# CAN_Adaptor.net
KiCad netlist of a schematic drawn in Altium Designer
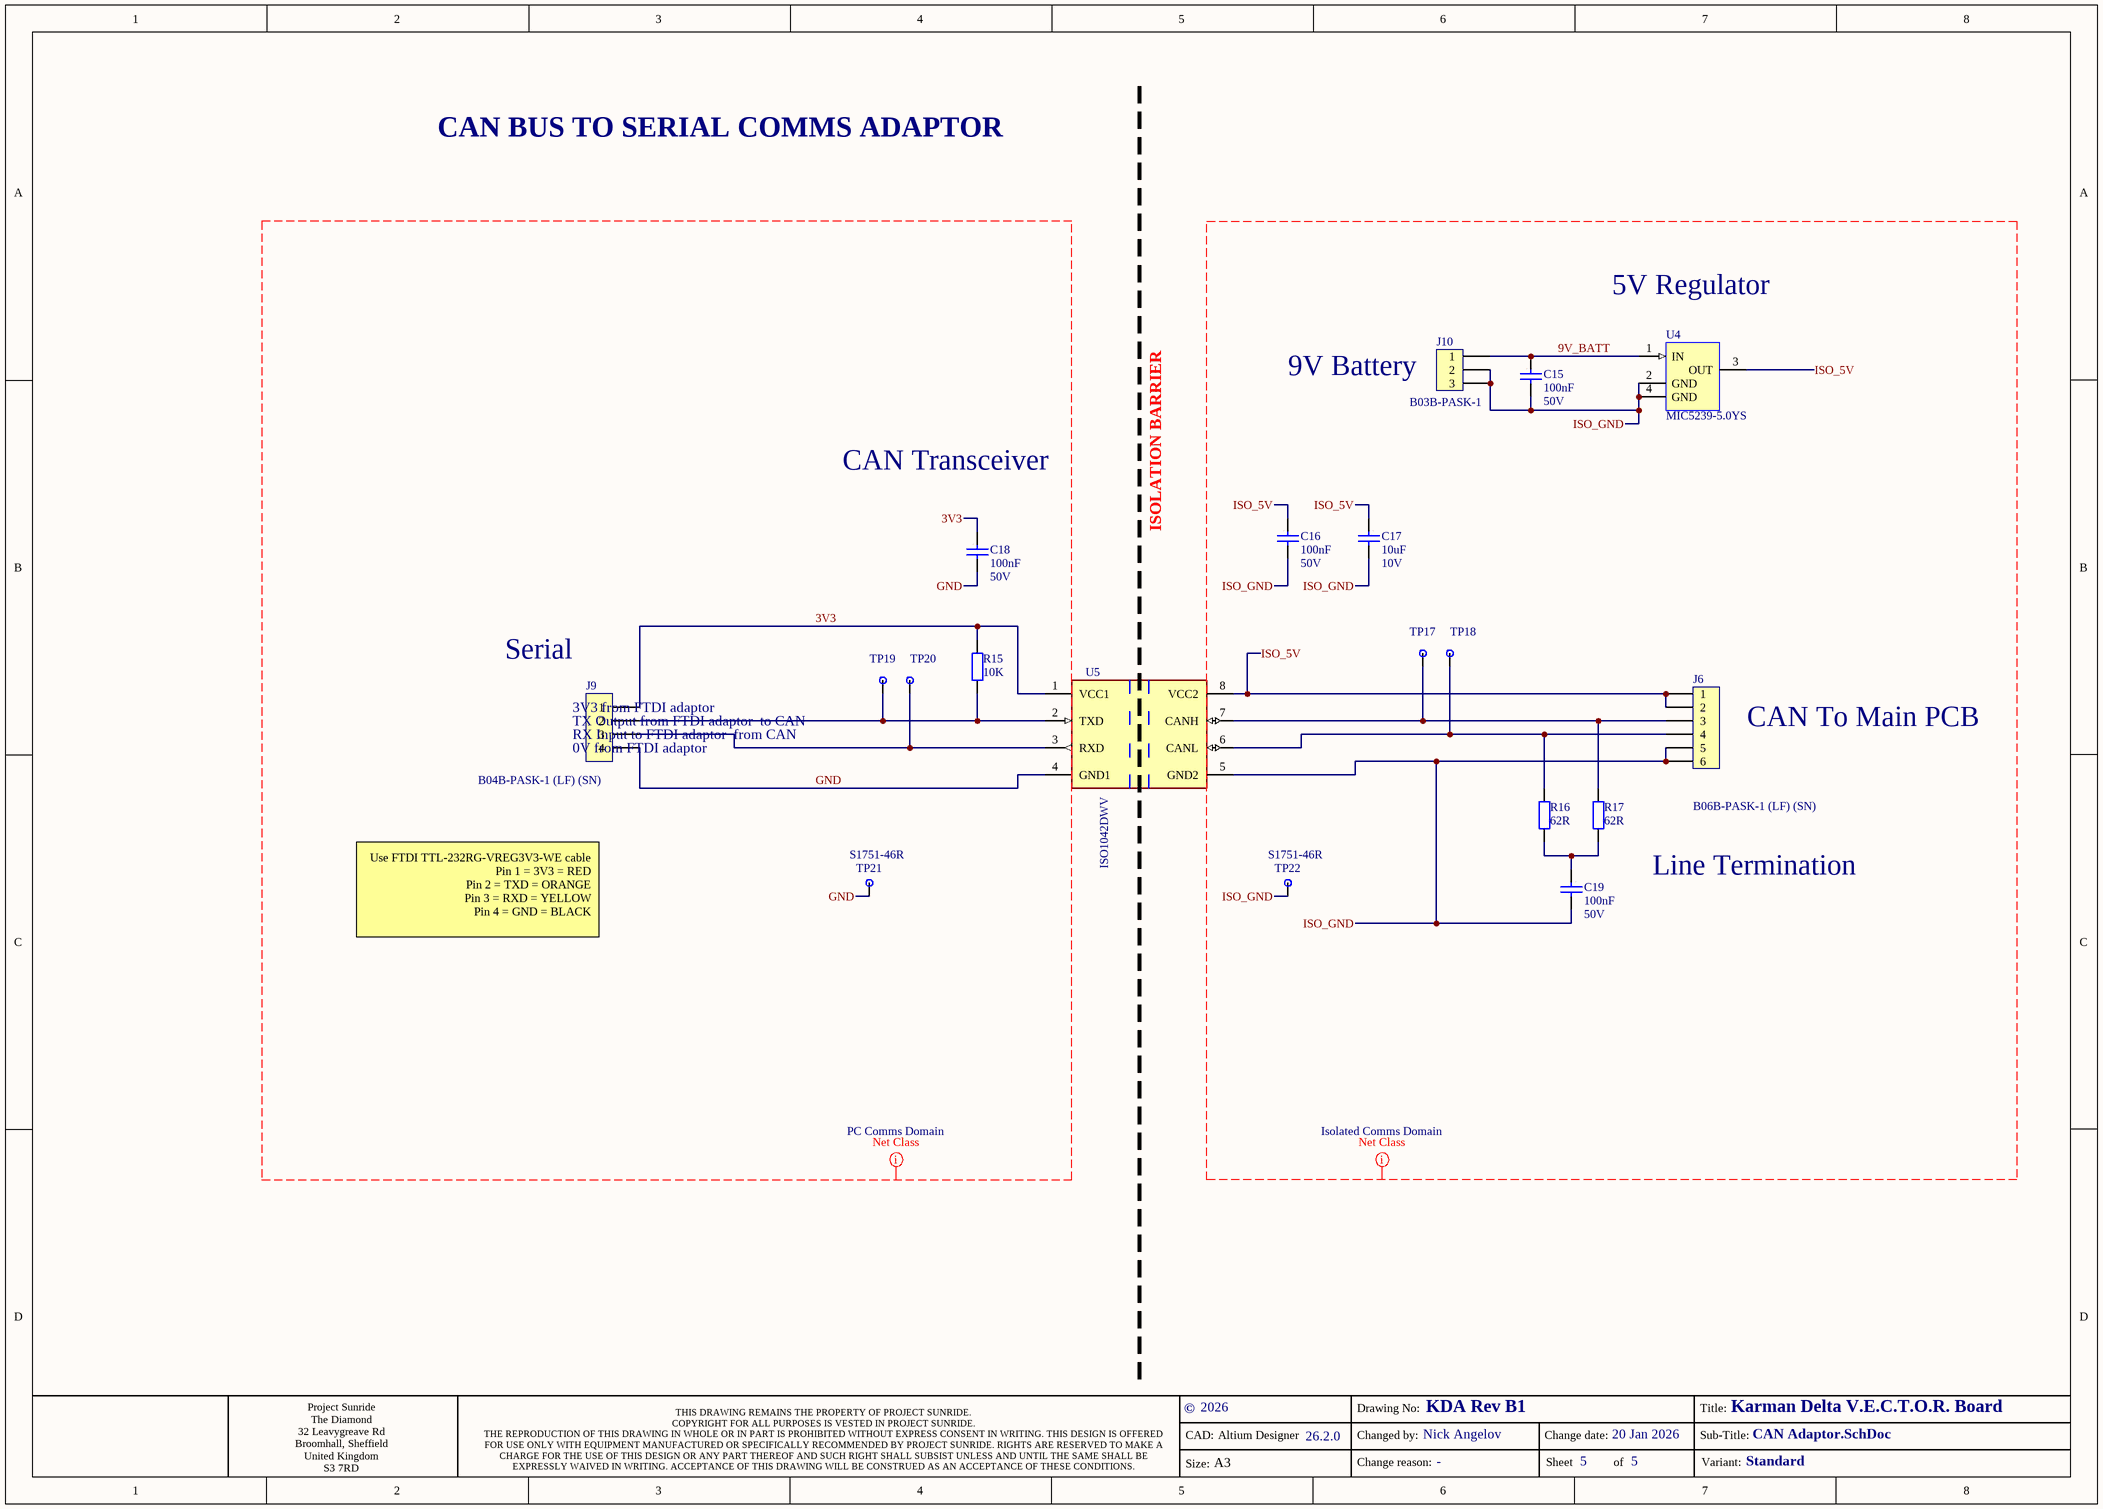
[diagram p0: CAN Adaptor.SchDoc]

(export (version "E")
  (design (tool "Eeschema 10.0.6"))
  (components
    (comp (ref "C15")
      (value "100nF")
      (footprint "CAPC1608X08L")
      (description "Capacitor MLC 100nF 50V X7R 10% CAPC1608X08M")
      (fields
        (field (name "VOLTAGE") "50V")
        (field (name "MANUFACTURER") "Murata")
        (field (name "MANUPARTNO") "GRM188R71H104KA93D")
      )
      (libsource (lib "Library") (part "CAP"))
    )
    (comp (ref "C16")
      (value "100nF")
      (footprint "CAPC1608X08L")
      (description "Capacitor MLC 100nF 50V X7R 10% CAPC1608X08M")
      (fields
        (field (name "VOLTAGE") "50V")
        (field (name "MANUFACTURER") "Murata")
        (field (name "MANUPARTNO") "GRM188R71H104KA93D")
      )
      (libsource (lib "Library") (part "CAP"))
    )
    (comp (ref "C17")
      (value "10uF")
      (footprint "CAPC2012X15M")
      (description "Capacitor MLC 10uF10V X7R 10% CAPC2012X15M")
      (fields
        (field (name "VOLTAGE") "10V")
        (field (name "MANUFACTURER") "Murata")
        (field (name "MANUPARTNO") "GRM21BR71A106KE51L")
      )
      (libsource (lib "") (part "CAP_1"))
    )
    (comp (ref "C18")
      (value "100nF")
      (footprint "CAPC1608X08L")
      (description "Capacitor MLC 100nF 50V X7R 10% CAPC1608X08M")
      (fields
        (field (name "VOLTAGE") "50V")
        (field (name "MANUFACTURER") "Murata")
        (field (name "MANUPARTNO") "GRM188R71H104KA93D")
      )
      (libsource (lib "Library") (part "CAP"))
    )
    (comp (ref "C19")
      (value "100nF")
      (footprint "CAPC1608X08L")
      (description "Capacitor MLC 100nF 50V X7R 10% CAPC1608X08M")
      (fields
        (field (name "VOLTAGE") "50V")
        (field (name "MANUFACTURER") "Murata")
        (field (name "MANUPARTNO") "GRM188R71H104KA93D")
      )
      (libsource (lib "") (part "CAP_1"))
    )
    (comp (ref "J6")
      (value "CAN To Main PCB")
      (footprint "B06B-PASK-1")
      (description "Connector 6 Way Vertical B06B-PASK-1 (LF) (SN) 2mm Pitch")
      (fields (field (name "MANUPARTNO") "B06B-PASK-1 (LF) (SN)") (field (name "MANUFACTURER") "JST"))
      (libsource (lib "Library") (part "CON6"))
    )
    (comp (ref "J9")
      (value "Serial")
      (footprint "B04B-PASK-1")
      (description "Connector 4 Way Vertical JST B04B-PASK-1 (LF) (SN) 2mm Pitch")
      (fields (field (name "MANUPARTNO") "B04B-PASK-1 (LF) (SN)") (field (name "MANUFACTURER") "JST"))
      (libsource (lib "Library") (part "CON4"))
    )
    (comp (ref "J10")
      (value "9V Battery")
      (footprint "B03B-PASK-1")
      (description "Connector 3 Way Vertical 2mm Pitch")
      (fields (field (name "MANUPARTNO") "B03B-PASK-1") (field (name "MANUFACTURER") "JST"))
      (libsource (lib "Library") (part "CON3"))
    )
    (comp (ref "R15")
      (value "10K")
      (footprint "RESC1608X06L")
      (description "SMD Chip Resistor, Thin Film, 10 kohm, 75 V, 0603 [1608 Metric], 100 mW, ± 0.1%, ERA3A Series")
      (fields (field (name "VOLTAGE") "75V") (field (name "MANUFACTURER") "Panasonic"))
      (libsource (lib "Library") (part "RESISTOR"))
    )
    (comp (ref "R16")
      (value "62R")
      (footprint "RESC1608X06L")
      (description "SMD Chip Resistor, Thick Film, 62 ohm, 75V, 0603 [1608 Metric], 100mW, ± 1%, RC Series")
      (fields (field (name "VOLTAGE") "75V") (field (name "POWER") "100mW"))
      (libsource (lib "Library") (part "RESISTOR"))
    )
    (comp (ref "R17")
      (value "Line Termination")
      (footprint "RESC1608X06L")
      (description "SMD Chip Resistor, Thick Film, 62 ohm, 75V, 0603 [1608 Metric], 100mW, ± 1%, RC Series")
      (fields
        (field (name "ALTIUM_VALUE") "62R")
        (field (name "VOLTAGE") "75V")
        (field (name "POWER") "100mW")
      )
      (libsource (lib "Library") (part "RESISTOR"))
    )
    (comp (ref "TP17")
      (value "TMS")
      (footprint "TP1")
      (description "Testpoint 1mm dia. Component side, no silk")
      (libsource (lib "Library") (part "TP1"))
    )
    (comp (ref "TP18")
      (value "TMS")
      (footprint "TP1")
      (description "Testpoint 1mm dia. Component side, no silk")
      (libsource (lib "Library") (part "TP1"))
    )
    (comp (ref "TP19")
      (value "TMS")
      (footprint "TP1")
      (description "Testpoint 1mm dia. Component side, no silk")
      (libsource (lib "Library") (part "TP1"))
    )
    (comp (ref "TP20")
      (value "TMS")
      (footprint "TP1")
      (description "Testpoint 1mm dia. Component side, no silk")
      (libsource (lib "Library") (part "TP1"))
    )
    (comp (ref "TP21")
      (value "GND")
      (footprint "S1751-46R")
      (description "PCB Test Point S1751 Series, Surface Mount")
      (fields (field (name "MANUPARTNO") "S1751-46R") (field (name "MANUFACTURER") "Harwin"))
      (libsource (lib "Library") (part "TP1-fitted"))
    )
    (comp (ref "TP22")
      (value "GND")
      (footprint "S1751-46R")
      (description "PCB Test Point S1751 Series, Surface Mount")
      (fields (field (name "MANUPARTNO") "S1751-46R") (field (name "MANUFACTURER") "Harwin"))
      (libsource (lib "Library") (part "TP1-fitted"))
    )
    (comp (ref "U4")
      (value "5V Regulator")
      (footprint "SOT230P700X170-4M")
      (description "IC Regulator LDO MIC5239-5.0YS SOT-223")
      (fields (field (name "MANUPARTNO") "MIC5239-5.0YS") (field (name "MANUFACTURER") "Micrel"))
      (libsource (lib "Library") (part "MIC5200"))
    )
    (comp (ref "U5")
      (value "CAN Transceiver")
      (footprint "FP-DWV0008A-IPC_C")
      (description "IC TRANSCEIVER FULL 1/1 8SOIC")
      (fields (field (name "MANUF PART NO") "ISO1042DWV"))
      (libsource (lib "Altium Content Vault") (part "909e5d76d32ef4d3bd4dfdc3f0018f8"))
    )
  )
  (nets
    (net (code "1") (name "/3V3") (class "Default")
      (node (ref "C18") (pin "1") (pinfunction "1_1") (pintype "passive"))
      (node (ref "J9") (pin "1") (pinfunction "1_1") (pintype "passive"))
      (node (ref "R15") (pin "2") (pinfunction "2_2") (pintype "passive"))
      (node (ref "U5") (pin "1") (pinfunction "VCC1_1") (pintype "power_in"))
    )
    (net (code "2") (name "/9V_BATT") (class "Default")
      (node (ref "C15") (pin "1") (pinfunction "1_1") (pintype "passive"))
      (node (ref "J10") (pin "1") (pinfunction "1_1") (pintype "passive"))
      (node (ref "U4") (pin "1") (pinfunction "IN_1") (pintype "input"))
    )
    (net (code "3") (name "/GND") (class "Default")
      (node (ref "C18") (pin "2") (pinfunction "2_2") (pintype "passive"))
      (node (ref "J9") (pin "4") (pinfunction "4_4") (pintype "passive"))
      (node (ref "TP21") (pin "1") (pintype "passive"))
      (node (ref "U5") (pin "4") (pinfunction "GND1_4") (pintype "power_in"))
    )
    (net (code "4") (name "/ISO_5V") (class "Default")
      (node (ref "C16") (pin "1") (pinfunction "1_1") (pintype "passive"))
      (node (ref "C17") (pin "1") (pinfunction "1_1") (pintype "passive"))
      (node (ref "J6") (pin "1") (pinfunction "1_1") (pintype "passive"))
      (node (ref "J6") (pin "2") (pinfunction "2_2") (pintype "passive"))
      (node (ref "U4") (pin "3") (pinfunction "OUT_3") (pintype "power_in"))
      (node (ref "U5") (pin "8") (pinfunction "VCC2_8") (pintype "power_in"))
    )
    (net (code "5") (name "/ISO_GND") (class "Default")
      (node (ref "C15") (pin "2") (pinfunction "2_2") (pintype "passive"))
      (node (ref "C16") (pin "2") (pinfunction "2_2") (pintype "passive"))
      (node (ref "C17") (pin "2") (pinfunction "2_2") (pintype "passive"))
      (node (ref "C19") (pin "2") (pinfunction "2_2") (pintype "passive"))
      (node (ref "J10") (pin "2") (pinfunction "2_2") (pintype "passive"))
      (node (ref "J10") (pin "3") (pinfunction "3_3") (pintype "passive"))
      (node (ref "J6") (pin "5") (pinfunction "5_5") (pintype "passive"))
      (node (ref "J6") (pin "6") (pinfunction "6_6") (pintype "passive"))
      (node (ref "TP22") (pin "1") (pintype "passive"))
      (node (ref "U4") (pin "2") (pinfunction "GND_2") (pintype "passive"))
      (node (ref "U4") (pin "4") (pinfunction "GND_4") (pintype "passive"))
      (node (ref "U5") (pin "5") (pinfunction "GND2_5") (pintype "power_in"))
    )
    (net (code "6") (name "Net-(C19-Pad1)") (class "Default")
      (node (ref "C19") (pin "1") (pinfunction "1_1") (pintype "passive"))
      (node (ref "R16") (pin "1") (pinfunction "1_1") (pintype "passive"))
      (node (ref "R17") (pin "1") (pinfunction "1_1") (pintype "passive"))
    )
    (net (code "7") (name "Net-(U5-CANH)") (class "Default")
      (node (ref "J6") (pin "3") (pinfunction "3_3") (pintype "passive"))
      (node (ref "R17") (pin "2") (pinfunction "2_2") (pintype "passive"))
      (node (ref "TP17") (pin "1") (pintype "passive"))
      (node (ref "U5") (pin "7") (pinfunction "CANH_7") (pintype "bidirectional"))
    )
    (net (code "8") (name "Net-(U5-CANL)") (class "Default")
      (node (ref "J6") (pin "4") (pinfunction "4_4") (pintype "passive"))
      (node (ref "R16") (pin "2") (pinfunction "2_2") (pintype "passive"))
      (node (ref "TP18") (pin "1") (pintype "passive"))
      (node (ref "U5") (pin "6") (pinfunction "CANL_6") (pintype "bidirectional"))
    )
    (net (code "9") (name "Net-(U5-RXD)") (class "Default")
      (node (ref "J9") (pin "3") (pinfunction "3_3") (pintype "passive"))
      (node (ref "TP20") (pin "1") (pintype "passive"))
      (node (ref "U5") (pin "3") (pinfunction "RXD_3") (pintype "output"))
    )
    (net (code "10") (name "Net-(U5-TXD)") (class "Default")
      (node (ref "J9") (pin "2") (pinfunction "2_2") (pintype "passive"))
      (node (ref "R15") (pin "1") (pinfunction "1_1") (pintype "passive"))
      (node (ref "TP19") (pin "1") (pintype "passive"))
      (node (ref "U5") (pin "2") (pinfunction "TXD_2") (pintype "input"))
    )
  )
)
